# CZTBoardV3.net
KiCad netlist of a schematic drawn in EAGLE
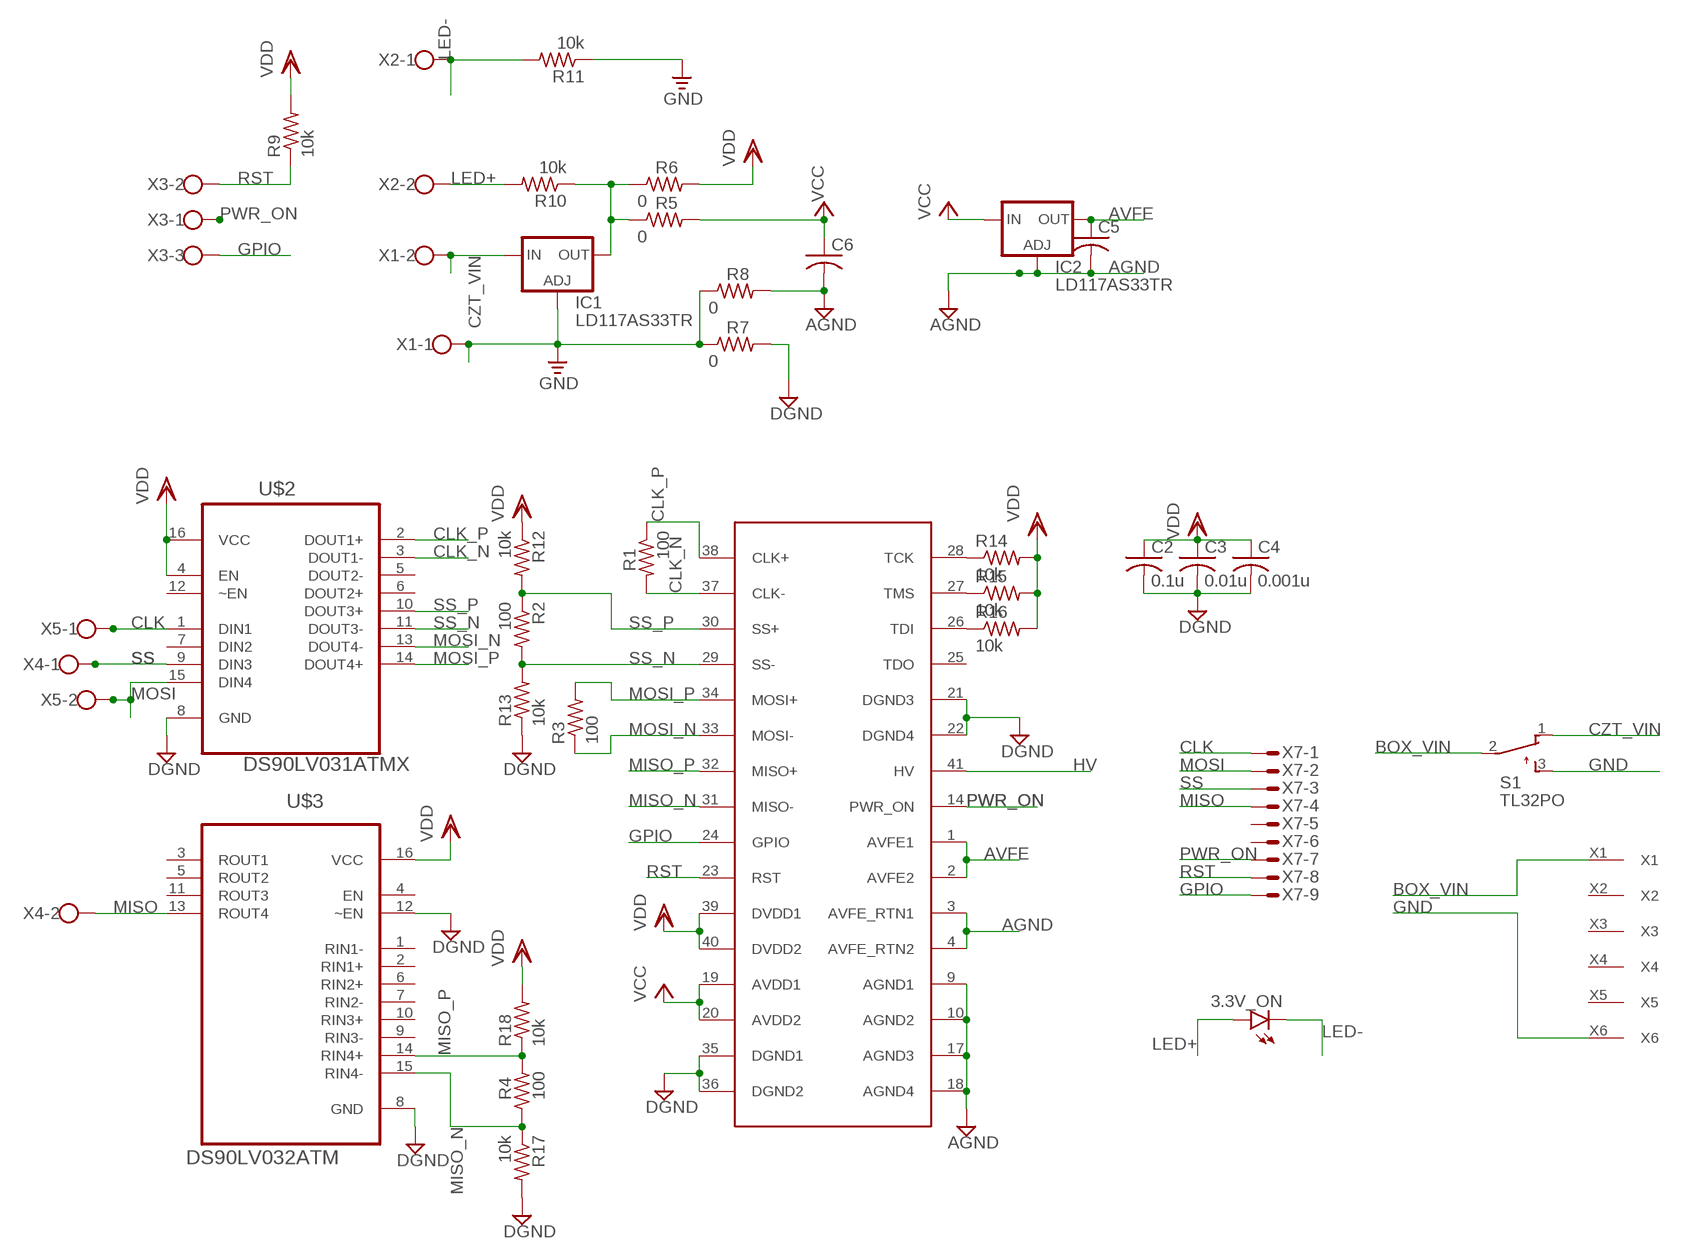
[diagram p0: schematic, sheet 1]

(export (version "E")
  (design (tool "Eeschema 10.0.6"))
  (components
    (comp (ref "3.3V_ON")
      (value "LED3MM")
      (footprint "eagle-import:LED3MM")
      (libsource (lib "eagle-import") (part "LED3MM"))
    )
    (comp (ref "C2")
      (value "0.1u")
      (footprint "eagle-import:C0805K")
      (libsource (lib "eagle-import") (part "C-USC0805K"))
    )
    (comp (ref "C3")
      (value "0.01u")
      (footprint "eagle-import:C0805K")
      (libsource (lib "eagle-import") (part "C-USC0805K"))
    )
    (comp (ref "C4")
      (value "0.001u")
      (footprint "eagle-import:C0805K")
      (libsource (lib "eagle-import") (part "C-USC0805K"))
    )
    (comp (ref "C5")
      (value "C-USC0805K")
      (footprint "eagle-import:C0805K")
      (libsource (lib "eagle-import") (part "C-USC0805K"))
    )
    (comp (ref "C6")
      (value "C-USC0805K")
      (footprint "eagle-import:C0805K")
      (libsource (lib "eagle-import") (part "C-USC0805K"))
    )
    (comp (ref "IC1")
      (value "LD117AS33TR")
      (footprint "eagle-import:SOT223")
      (libsource (lib "eagle-import") (part "LD117A?S33TR"))
    )
    (comp (ref "IC2")
      (value "LD117AS33TR")
      (footprint "eagle-import:SOT223")
      (libsource (lib "eagle-import") (part "LD117A?S33TR"))
    )
    (comp (ref "R1")
      (value "100")
      (footprint "eagle-import:R1206")
      (libsource (lib "eagle-import") (part "R-US_R1206"))
    )
    (comp (ref "R2")
      (value "100")
      (footprint "eagle-import:R1206")
      (libsource (lib "eagle-import") (part "R-US_R1206"))
    )
    (comp (ref "R3")
      (value "100")
      (footprint "eagle-import:R1206")
      (libsource (lib "eagle-import") (part "R-US_R1206"))
    )
    (comp (ref "R4")
      (value "100")
      (footprint "eagle-import:R1206")
      (libsource (lib "eagle-import") (part "R-US_R1206"))
    )
    (comp (ref "R5")
      (value "0")
      (footprint "eagle-import:R1206")
      (libsource (lib "eagle-import") (part "R-US_R1206"))
    )
    (comp (ref "R6")
      (value "0")
      (footprint "eagle-import:R1206")
      (libsource (lib "eagle-import") (part "R-US_R1206"))
    )
    (comp (ref "R7")
      (value "0")
      (footprint "eagle-import:R1206")
      (libsource (lib "eagle-import") (part "R-US_R1206"))
    )
    (comp (ref "R8")
      (value "0")
      (footprint "eagle-import:R1206")
      (libsource (lib "eagle-import") (part "R-US_R1206"))
    )
    (comp (ref "R9")
      (value "10k")
      (footprint "eagle-import:R1206")
      (libsource (lib "eagle-import") (part "R-US_R1206"))
    )
    (comp (ref "R10")
      (value "10k")
      (footprint "eagle-import:R1206")
      (libsource (lib "eagle-import") (part "R-US_R1206"))
    )
    (comp (ref "R11")
      (value "10k")
      (footprint "eagle-import:R1206")
      (libsource (lib "eagle-import") (part "R-US_R1206"))
    )
    (comp (ref "R12")
      (value "10k")
      (footprint "eagle-import:R1206")
      (libsource (lib "eagle-import") (part "R-US_R1206"))
    )
    (comp (ref "R13")
      (value "10k")
      (footprint "eagle-import:R1206")
      (libsource (lib "eagle-import") (part "R-US_R1206"))
    )
    (comp (ref "R14")
      (value "10k")
      (footprint "eagle-import:R1206")
      (libsource (lib "eagle-import") (part "R-US_R1206"))
    )
    (comp (ref "R15")
      (value "10k")
      (footprint "eagle-import:R1206")
      (libsource (lib "eagle-import") (part "R-US_R1206"))
    )
    (comp (ref "R16")
      (value "10k")
      (footprint "eagle-import:R1206")
      (libsource (lib "eagle-import") (part "R-US_R1206"))
    )
    (comp (ref "R17")
      (value "10k")
      (footprint "eagle-import:R1206")
      (libsource (lib "eagle-import") (part "R-US_R1206"))
    )
    (comp (ref "R18")
      (value "10k")
      (footprint "eagle-import:R1206")
      (libsource (lib "eagle-import") (part "R-US_R1206"))
    )
    (comp (ref "S1")
      (value "TL32PO")
      (footprint "eagle-import:TL3XPO")
      (libsource (lib "eagle-import") (part "TL32PO"))
    )
    (comp (ref "U$1")
      (value "ORBOTECH_OMS40G256")
      (footprint "eagle-import:ORBOTECH_OMS40G256")
      (libsource (lib "eagle-import") (part "ORBOTECH_OMS40G256"))
    )
    (comp (ref "U$2")
      (value "DS90LV031ATMX")
      (footprint "eagle-import:SOIC127P600X175-16N")
      (libsource (lib "eagle-import") (part "DS90LV031ATMX"))
    )
    (comp (ref "U$3")
      (value "DS90LV032ATM")
      (footprint "eagle-import:SOIC127P600X175-16N")
      (libsource (lib "eagle-import") (part "DS90LV032ATM"))
    )
    (comp (ref "X1")
      (value "W237-102")
      (footprint "eagle-import:W237-102")
      (fields (field (name "MPN") "237-102"))
      (libsource (lib "eagle-import") (part "W237-102"))
    )
    (comp (ref "X2")
      (value "W237-102")
      (footprint "eagle-import:W237-102")
      (fields (field (name "MPN") "237-102"))
      (libsource (lib "eagle-import") (part "W237-102"))
    )
    (comp (ref "X3")
      (value "W237-103")
      (footprint "eagle-import:W237-103")
      (fields (field (name "MPN") "237-103"))
      (libsource (lib "eagle-import") (part "W237-103"))
    )
    (comp (ref "X4")
      (value "W237-102")
      (footprint "eagle-import:W237-102")
      (fields (field (name "MPN") "237-102"))
      (libsource (lib "eagle-import") (part "W237-102"))
    )
    (comp (ref "X5")
      (value "W237-102")
      (footprint "eagle-import:W237-102")
      (fields (field (name "MPN") "237-102"))
      (libsource (lib "eagle-import") (part "W237-102"))
    )
    (comp (ref "X6")
      (value "GX16")
      (footprint "eagle-import:GX16")
      (libsource (lib "eagle-import") (part "GX16"))
    )
    (comp (ref "X7")
      (value "M09VS")
      (footprint "eagle-import:M09V")
      (libsource (lib "eagle-import") (part "M09?SV"))
    )
  )
  (nets
    (net (code "1") (name "/AVFE") (class "Default")
      (node (ref "C5") (pin "1") (pinfunction "1_1") (pintype "passive"))
      (node (ref "IC2") (pin "4") (pinfunction "OUT_4") (pintype "passive"))
      (node (ref "U$1") (pin "1") (pinfunction "AVFE1_1") (pintype "bidirectional"))
      (node (ref "U$1") (pin "2") (pinfunction "AVFE2_2") (pintype "bidirectional"))
    )
    (net (code "2") (name "/BOX_VIN") (class "Default")
      (node (ref "S1") (pin "2") (pinfunction "P_2") (pintype "passive"))
      (node (ref "X6") (pin "X1") (pinfunction "X1_X1") (pintype "bidirectional"))
    )
    (net (code "3") (name "/CLK") (class "Default")
      (node (ref "U$2") (pin "1") (pinfunction "DIN1_1") (pintype "input"))
      (node (ref "X5") (pin "1") (pinfunction "KL_1") (pintype "passive"))
      (node (ref "X7") (pin "1") (pinfunction "M_1") (pintype "passive"))
    )
    (net (code "4") (name "/CLK_N") (class "Default")
      (node (ref "R1") (pin "2") (pinfunction "2_2") (pintype "passive"))
      (node (ref "U$1") (pin "37") (pinfunction "CLK-_37") (pintype "bidirectional"))
      (node (ref "U$2") (pin "3") (pinfunction "DOUT1-_3") (pintype "output"))
    )
    (net (code "5") (name "/CLK_P") (class "Default")
      (node (ref "R1") (pin "1") (pinfunction "1_1") (pintype "passive"))
      (node (ref "U$1") (pin "38") (pinfunction "CLK+_38") (pintype "bidirectional"))
      (node (ref "U$2") (pin "2") (pinfunction "DOUT1+_2") (pintype "output"))
    )
    (net (code "6") (name "/CZT_VIN") (class "Default")
      (node (ref "IC1") (pin "3") (pinfunction "IN_3") (pintype "input"))
      (node (ref "S1") (pin "1") (pinfunction "O_1") (pintype "passive"))
      (node (ref "X1") (pin "2") (pinfunction "KL_2") (pintype "passive"))
    )
    (net (code "7") (name "/GPIO") (class "Default")
      (node (ref "U$1") (pin "24") (pinfunction "GPIO_24") (pintype "bidirectional"))
      (node (ref "X3") (pin "3") (pinfunction "KL_3") (pintype "passive"))
      (node (ref "X7") (pin "9") (pinfunction "M_9") (pintype "passive"))
    )
    (net (code "8") (name "/HV") (class "Default")
      (node (ref "U$1") (pin "41") (pinfunction "HV_41") (pintype "bidirectional"))
    )
    (net (code "9") (name "/LED+") (class "Default")
      (node (ref "3.3V_ON") (pin "A") (pinfunction "A_A") (pintype "passive"))
      (node (ref "R10") (pin "2") (pinfunction "2_2") (pintype "passive"))
      (node (ref "X2") (pin "2") (pinfunction "KL_2") (pintype "passive"))
    )
    (net (code "10") (name "/LED-") (class "Default")
      (node (ref "3.3V_ON") (pin "K") (pinfunction "C_K") (pintype "passive"))
      (node (ref "R11") (pin "2") (pinfunction "2_2") (pintype "passive"))
      (node (ref "X2") (pin "1") (pinfunction "KL_1") (pintype "passive"))
    )
    (net (code "11") (name "/MISO") (class "Default")
      (node (ref "U$3") (pin "13") (pinfunction "ROUT4_13") (pintype "output"))
      (node (ref "X4") (pin "2") (pinfunction "KL_2") (pintype "passive"))
      (node (ref "X7") (pin "4") (pinfunction "M_4") (pintype "passive"))
    )
    (net (code "12") (name "/MISO_N") (class "Default")
      (node (ref "R17") (pin "1") (pinfunction "1_1") (pintype "passive"))
      (node (ref "R4") (pin "1") (pinfunction "1_1") (pintype "passive"))
      (node (ref "U$1") (pin "31") (pinfunction "MISO-_31") (pintype "bidirectional"))
      (node (ref "U$3") (pin "15") (pinfunction "RIN4-_15") (pintype "input"))
    )
    (net (code "13") (name "/MISO_P") (class "Default")
      (node (ref "R18") (pin "1") (pinfunction "1_1") (pintype "passive"))
      (node (ref "R4") (pin "2") (pinfunction "2_2") (pintype "passive"))
      (node (ref "U$1") (pin "32") (pinfunction "MISO+_32") (pintype "bidirectional"))
      (node (ref "U$3") (pin "14") (pinfunction "RIN4+_14") (pintype "input"))
    )
    (net (code "14") (name "/MOSI") (class "Default")
      (node (ref "U$2") (pin "15") (pinfunction "DIN4_15") (pintype "input"))
      (node (ref "X5") (pin "2") (pinfunction "KL_2") (pintype "passive"))
      (node (ref "X7") (pin "2") (pinfunction "M_2") (pintype "passive"))
    )
    (net (code "15") (name "/MOSI_N") (class "Default")
      (node (ref "R3") (pin "1") (pinfunction "1_1") (pintype "passive"))
      (node (ref "U$1") (pin "33") (pinfunction "MOSI-_33") (pintype "bidirectional"))
      (node (ref "U$2") (pin "13") (pinfunction "DOUT4-_13") (pintype "output"))
    )
    (net (code "16") (name "/MOSI_P") (class "Default")
      (node (ref "R3") (pin "2") (pinfunction "2_2") (pintype "passive"))
      (node (ref "U$1") (pin "34") (pinfunction "MOSI+_34") (pintype "bidirectional"))
      (node (ref "U$2") (pin "14") (pinfunction "DOUT4+_14") (pintype "output"))
    )
    (net (code "17") (name "/PWR_ON") (class "Default")
      (node (ref "U$1") (pin "14") (pinfunction "PWR_ON_14") (pintype "bidirectional"))
      (node (ref "X3") (pin "1") (pinfunction "KL_1") (pintype "passive"))
      (node (ref "X7") (pin "7") (pinfunction "M_7") (pintype "passive"))
    )
    (net (code "18") (name "/RST") (class "Default")
      (node (ref "R9") (pin "1") (pinfunction "1_1") (pintype "passive"))
      (node (ref "U$1") (pin "23") (pinfunction "RST_23") (pintype "bidirectional"))
      (node (ref "X3") (pin "2") (pinfunction "KL_2") (pintype "passive"))
      (node (ref "X7") (pin "8") (pinfunction "M_8") (pintype "passive"))
    )
    (net (code "19") (name "/SS") (class "Default")
      (node (ref "U$2") (pin "9") (pinfunction "DIN3_9") (pintype "input"))
      (node (ref "X4") (pin "1") (pinfunction "KL_1") (pintype "passive"))
      (node (ref "X7") (pin "3") (pinfunction "M_3") (pintype "passive"))
    )
    (net (code "20") (name "/SS_N") (class "Default")
      (node (ref "R13") (pin "2") (pinfunction "2_2") (pintype "passive"))
      (node (ref "R2") (pin "2") (pinfunction "2_2") (pintype "passive"))
      (node (ref "U$1") (pin "29") (pinfunction "SS-_29") (pintype "bidirectional"))
      (node (ref "U$2") (pin "11") (pinfunction "DOUT3-_11") (pintype "output"))
    )
    (net (code "21") (name "/SS_P") (class "Default")
      (node (ref "R12") (pin "2") (pinfunction "2_2") (pintype "passive"))
      (node (ref "R2") (pin "1") (pinfunction "1_1") (pintype "passive"))
      (node (ref "U$1") (pin "30") (pinfunction "SS+_30") (pintype "bidirectional"))
      (node (ref "U$2") (pin "10") (pinfunction "DOUT3+_10") (pintype "output"))
    )
    (net (code "22") (name "AGND") (class "Default")
      (node (ref "C5") (pin "2") (pinfunction "2_2") (pintype "passive"))
      (node (ref "C6") (pin "2") (pinfunction "2_2") (pintype "passive"))
      (node (ref "IC2") (pin "1") (pinfunction "ADJ_1") (pintype "input"))
      (node (ref "R8") (pin "2") (pinfunction "2_2") (pintype "passive"))
      (node (ref "U$1") (pin "10") (pinfunction "AGND2_10") (pintype "bidirectional"))
      (node (ref "U$1") (pin "17") (pinfunction "AGND3_17") (pintype "bidirectional"))
      (node (ref "U$1") (pin "18") (pinfunction "AGND4_18") (pintype "bidirectional"))
      (node (ref "U$1") (pin "3") (pinfunction "AVFE_RTN1_3") (pintype "bidirectional"))
      (node (ref "U$1") (pin "4") (pinfunction "AVFE_RTN2_4") (pintype "bidirectional"))
      (node (ref "U$1") (pin "9") (pinfunction "AGND1_9") (pintype "bidirectional"))
    )
    (net (code "23") (name "DGND") (class "Default")
      (node (ref "C2") (pin "2") (pinfunction "2_2") (pintype "passive"))
      (node (ref "C3") (pin "2") (pinfunction "2_2") (pintype "passive"))
      (node (ref "C4") (pin "2") (pinfunction "2_2") (pintype "passive"))
      (node (ref "R13") (pin "1") (pinfunction "1_1") (pintype "passive"))
      (node (ref "R17") (pin "2") (pinfunction "2_2") (pintype "passive"))
      (node (ref "R7") (pin "2") (pinfunction "2_2") (pintype "passive"))
      (node (ref "U$1") (pin "21") (pinfunction "DGND3_21") (pintype "bidirectional"))
      (node (ref "U$1") (pin "22") (pinfunction "DGND4_22") (pintype "bidirectional"))
      (node (ref "U$1") (pin "35") (pinfunction "DGND1_35") (pintype "bidirectional"))
      (node (ref "U$1") (pin "36") (pinfunction "DGND2_36") (pintype "bidirectional"))
      (node (ref "U$2") (pin "8") (pinfunction "GND_8") (pintype "passive"))
      (node (ref "U$3") (pin "12") (pinfunction "~{EN}_12") (pintype "input"))
      (node (ref "U$3") (pin "8") (pinfunction "GND_8") (pintype "passive"))
    )
    (net (code "24") (name "GND") (class "Default")
      (node (ref "IC1") (pin "1") (pinfunction "ADJ_1") (pintype "input"))
      (node (ref "R11") (pin "1") (pinfunction "1_1") (pintype "passive"))
      (node (ref "R7") (pin "1") (pinfunction "1_1") (pintype "passive"))
      (node (ref "R8") (pin "1") (pinfunction "1_1") (pintype "passive"))
      (node (ref "S1") (pin "3") (pinfunction "S_3") (pintype "passive"))
      (node (ref "X1") (pin "1") (pinfunction "KL_1") (pintype "passive"))
      (node (ref "X6") (pin "X6") (pinfunction "X6_X6") (pintype "bidirectional"))
    )
    (net (code "25") (name "Net-(IC1-OUT)") (class "Default")
      (node (ref "IC1") (pin "4") (pinfunction "OUT_4") (pintype "passive"))
      (node (ref "R10") (pin "1") (pinfunction "1_1") (pintype "passive"))
      (node (ref "R5") (pin "1") (pinfunction "1_1") (pintype "passive"))
      (node (ref "R6") (pin "1") (pinfunction "1_1") (pintype "passive"))
    )
    (net (code "26") (name "Net-(U$1-TCK)") (class "Default")
      (node (ref "R14") (pin "1") (pinfunction "1_1") (pintype "passive"))
      (node (ref "U$1") (pin "28") (pinfunction "TCK_28") (pintype "bidirectional"))
    )
    (net (code "27") (name "Net-(U$1-TDI)") (class "Default")
      (node (ref "R16") (pin "1") (pinfunction "1_1") (pintype "passive"))
      (node (ref "U$1") (pin "26") (pinfunction "TDI_26") (pintype "bidirectional"))
    )
    (net (code "28") (name "Net-(U$1-TMS)") (class "Default")
      (node (ref "R15") (pin "1") (pinfunction "1_1") (pintype "passive"))
      (node (ref "U$1") (pin "27") (pinfunction "TMS_27") (pintype "bidirectional"))
    )
    (net (code "29") (name "VCC") (class "Default")
      (node (ref "C6") (pin "1") (pinfunction "1_1") (pintype "passive"))
      (node (ref "IC2") (pin "3") (pinfunction "IN_3") (pintype "input"))
      (node (ref "R5") (pin "2") (pinfunction "2_2") (pintype "passive"))
      (node (ref "U$1") (pin "19") (pinfunction "AVDD1_19") (pintype "bidirectional"))
      (node (ref "U$1") (pin "20") (pinfunction "AVDD2_20") (pintype "bidirectional"))
    )
    (net (code "30") (name "VDD") (class "Default")
      (node (ref "C2") (pin "1") (pinfunction "1_1") (pintype "passive"))
      (node (ref "C3") (pin "1") (pinfunction "1_1") (pintype "passive"))
      (node (ref "C4") (pin "1") (pinfunction "1_1") (pintype "passive"))
      (node (ref "R12") (pin "1") (pinfunction "1_1") (pintype "passive"))
      (node (ref "R14") (pin "2") (pinfunction "2_2") (pintype "passive"))
      (node (ref "R15") (pin "2") (pinfunction "2_2") (pintype "passive"))
      (node (ref "R16") (pin "2") (pinfunction "2_2") (pintype "passive"))
      (node (ref "R18") (pin "2") (pinfunction "2_2") (pintype "passive"))
      (node (ref "R6") (pin "2") (pinfunction "2_2") (pintype "passive"))
      (node (ref "R9") (pin "2") (pinfunction "2_2") (pintype "passive"))
      (node (ref "U$1") (pin "39") (pinfunction "DVDD1_39") (pintype "bidirectional"))
      (node (ref "U$1") (pin "40") (pinfunction "DVDD2_40") (pintype "bidirectional"))
      (node (ref "U$2") (pin "16") (pinfunction "VCC_16") (pintype "power_in"))
      (node (ref "U$2") (pin "4") (pinfunction "EN_4") (pintype "input"))
      (node (ref "U$3") (pin "16") (pinfunction "VCC_16") (pintype "power_in"))
    )
    (net (code "31") (name "unconnected-(U$1-TDO-Pad25)") (class "Default")
      (node (ref "U$1") (pin "25") (pinfunction "TDO_25") (pintype "bidirectional"))
    )
    (net (code "32") (name "unconnected-(U$2-DIN2-Pad7)") (class "Default")
      (node (ref "U$2") (pin "7") (pinfunction "DIN2_7") (pintype "input"))
    )
    (net (code "33") (name "unconnected-(U$2-DOUT2+-Pad6)") (class "Default")
      (node (ref "U$2") (pin "6") (pinfunction "DOUT2+_6") (pintype "output"))
    )
    (net (code "34") (name "unconnected-(U$2-DOUT2--Pad5)") (class "Default")
      (node (ref "U$2") (pin "5") (pinfunction "DOUT2-_5") (pintype "output"))
    )
    (net (code "35") (name "unconnected-(U$2-~{EN}-Pad12)") (class "Default")
      (node (ref "U$2") (pin "12") (pinfunction "~{EN}_12") (pintype "input"))
    )
    (net (code "36") (name "unconnected-(U$3-EN-Pad4)") (class "Default")
      (node (ref "U$3") (pin "4") (pinfunction "EN_4") (pintype "input"))
    )
    (net (code "37") (name "unconnected-(U$3-RIN1+-Pad2)") (class "Default")
      (node (ref "U$3") (pin "2") (pinfunction "RIN1+_2") (pintype "input"))
    )
    (net (code "38") (name "unconnected-(U$3-RIN1--Pad1)") (class "Default")
      (node (ref "U$3") (pin "1") (pinfunction "RIN1-_1") (pintype "input"))
    )
    (net (code "39") (name "unconnected-(U$3-RIN2+-Pad6)") (class "Default")
      (node (ref "U$3") (pin "6") (pinfunction "RIN2+_6") (pintype "input"))
    )
    (net (code "40") (name "unconnected-(U$3-RIN2--Pad7)") (class "Default")
      (node (ref "U$3") (pin "7") (pinfunction "RIN2-_7") (pintype "input"))
    )
    (net (code "41") (name "unconnected-(U$3-RIN3+-Pad10)") (class "Default")
      (node (ref "U$3") (pin "10") (pinfunction "RIN3+_10") (pintype "input"))
    )
    (net (code "42") (name "unconnected-(U$3-RIN3--Pad9)") (class "Default")
      (node (ref "U$3") (pin "9") (pinfunction "RIN3-_9") (pintype "input"))
    )
    (net (code "43") (name "unconnected-(U$3-ROUT1-Pad3)") (class "Default")
      (node (ref "U$3") (pin "3") (pinfunction "ROUT1_3") (pintype "output"))
    )
    (net (code "44") (name "unconnected-(U$3-ROUT2-Pad5)") (class "Default")
      (node (ref "U$3") (pin "5") (pinfunction "ROUT2_5") (pintype "output"))
    )
    (net (code "45") (name "unconnected-(U$3-ROUT3-Pad11)") (class "Default")
      (node (ref "U$3") (pin "11") (pinfunction "ROUT3_11") (pintype "output"))
    )
    (net (code "46") (name "unconnected-(X6-PadX2)") (class "Default")
      (node (ref "X6") (pin "X2") (pinfunction "X2_X2") (pintype "bidirectional"))
    )
    (net (code "47") (name "unconnected-(X6-PadX3)") (class "Default")
      (node (ref "X6") (pin "X3") (pinfunction "X3_X3") (pintype "bidirectional"))
    )
    (net (code "48") (name "unconnected-(X6-PadX4)") (class "Default")
      (node (ref "X6") (pin "X4") (pinfunction "X4_X4") (pintype "bidirectional"))
    )
    (net (code "49") (name "unconnected-(X6-PadX5)") (class "Default")
      (node (ref "X6") (pin "X5") (pinfunction "X5_X5") (pintype "bidirectional"))
    )
    (net (code "50") (name "unconnected-(X7E-M-Pad5)") (class "Default")
      (node (ref "X7") (pin "5") (pinfunction "M_5") (pintype "passive"))
    )
    (net (code "51") (name "unconnected-(X7F-M-Pad6)") (class "Default")
      (node (ref "X7") (pin "6") (pinfunction "M_6") (pintype "passive"))
    )
  )
)
